# WEMOSD1R1_MATRIX64X32_RGB.net
KiCad netlist of a schematic drawn in Altium Designer
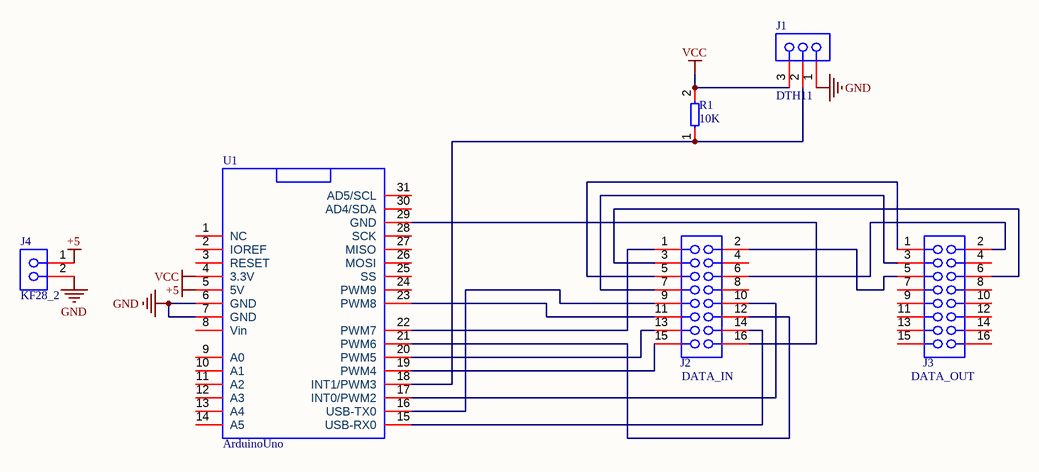
[diagram p0: WEMOSD1R1_MATRIX64X32_RGB.SchDoc]

(export (version "E")
  (design (tool "Eeschema 10.0.6"))
  (components
    (comp (ref "J1")
      (value "DTH11")
      (footprint "Header 3x1 TH Pitch 2.54mm")
      (libsource (lib "Lib31082020") (part "Header 3x1 TH Pitch 2.54mm"))
    )
    (comp (ref "J2")
      (value "DATA_IN")
      (footprint "Header 8x2 TH Pitch 2.54mm")
      (libsource (lib "Lib31082020") (part "Header 8x2 TH Pitch 2.54mm"))
    )
    (comp (ref "J3")
      (value "DATA_OUT")
      (footprint "Header 8x2 TH Pitch 2.54mm")
      (libsource (lib "Lib31082020") (part "Header 8x2 TH Pitch 2.54mm"))
    )
    (comp (ref "J4")
      (value "KF28_2")
      (footprint "HEADER_KF128_2_5.08MM")
      (libsource (lib "Lib31082020") (part "HEADER_KF128_2_5.08MM"))
    )
    (comp (ref "R1")
      (value "10K")
      (footprint "RES-0.25W-H-MF")
      (libsource (lib "Lib31082020") (part "Resistors THD"))
    )
    (comp (ref "U1")
      (value "ArduinoUno")
      (footprint "ARDUINO_UNO_PIN_PACK")
      (libsource (lib "Lib31082020") (part "ArduinoUno"))
    )
  )
  (nets
    (net (code "1") (name "+5") (class "Default")
      (node (ref "J4") (pin "1") (pinfunction "1_1") (pintype "passive"))
      (node (ref "U1") (pin "5") (pinfunction "5V_5") (pintype "passive"))
    )
    (net (code "2") (name "GND") (class "Default")
      (node (ref "J1") (pin "1") (pinfunction "1_1") (pintype "passive"))
      (node (ref "J4") (pin "2") (pinfunction "2_2") (pintype "passive"))
      (node (ref "U1") (pin "6") (pinfunction "GND_6") (pintype "passive"))
      (node (ref "U1") (pin "7") (pinfunction "GND_7") (pintype "passive"))
    )
    (net (code "3") (name "Net-(J2-Pad2)") (class "Default")
      (node (ref "J2") (pin "2") (pinfunction "2_2") (pintype "passive"))
      (node (ref "J3") (pin "5") (pinfunction "5_5") (pintype "passive"))
    )
    (net (code "4") (name "Net-(J2-Pad3)") (class "Default")
      (node (ref "J2") (pin "3") (pinfunction "3_3") (pintype "passive"))
      (node (ref "J3") (pin "6") (pinfunction "6_6") (pintype "passive"))
    )
    (net (code "5") (name "Net-(J2-Pad5)") (class "Default")
      (node (ref "J2") (pin "5") (pinfunction "5_5") (pintype "passive"))
      (node (ref "J3") (pin "1") (pinfunction "1_1") (pintype "passive"))
    )
    (net (code "6") (name "Net-(J2-Pad6)") (class "Default")
      (node (ref "J2") (pin "6") (pinfunction "6_6") (pintype "passive"))
      (node (ref "J3") (pin "2") (pinfunction "2_2") (pintype "passive"))
    )
    (net (code "7") (name "Net-(J2-Pad7)") (class "Default")
      (node (ref "J2") (pin "7") (pinfunction "7_7") (pintype "passive"))
      (node (ref "J3") (pin "3") (pinfunction "3_3") (pintype "passive"))
    )
    (net (code "8") (name "Net-(J2-Pad16)") (class "Default")
      (node (ref "J2") (pin "16") (pinfunction "16_16") (pintype "passive"))
      (node (ref "U1") (pin "29") (pinfunction "GND_29") (pintype "passive"))
    )
    (net (code "9") (name "Net-(U1-INT0{slash}PWM2)") (class "Default")
      (node (ref "J2") (pin "10") (pinfunction "10_10") (pintype "passive"))
      (node (ref "U1") (pin "17") (pinfunction "INT0/PWM2_17") (pintype "passive"))
    )
    (net (code "10") (name "Net-(U1-INT1{slash}PWM3)") (class "Default")
      (node (ref "J1") (pin "2") (pinfunction "2_2") (pintype "passive"))
      (node (ref "R1") (pin "1") (pinfunction "1_1") (pintype "passive"))
      (node (ref "U1") (pin "18") (pinfunction "INT1/PWM3_18") (pintype "passive"))
    )
    (net (code "11") (name "Net-(U1-PWM4)") (class "Default")
      (node (ref "J2") (pin "15") (pinfunction "15_15") (pintype "passive"))
      (node (ref "U1") (pin "19") (pinfunction "PWM4_19") (pintype "passive"))
    )
    (net (code "12") (name "Net-(U1-PWM5)") (class "Default")
      (node (ref "J2") (pin "13") (pinfunction "13_13") (pintype "passive"))
      (node (ref "U1") (pin "20") (pinfunction "PWM5_20") (pintype "passive"))
    )
    (net (code "13") (name "Net-(U1-PWM6)") (class "Default")
      (node (ref "J2") (pin "12") (pinfunction "12_12") (pintype "passive"))
      (node (ref "U1") (pin "21") (pinfunction "PWM6_21") (pintype "passive"))
    )
    (net (code "14") (name "Net-(U1-PWM7)") (class "Default")
      (node (ref "J2") (pin "1") (pinfunction "1_1") (pintype "passive"))
      (node (ref "U1") (pin "22") (pinfunction "PWM7_22") (pintype "passive"))
    )
    (net (code "15") (name "Net-(U1-PWM8)") (class "Default")
      (node (ref "J2") (pin "11") (pinfunction "11_11") (pintype "passive"))
      (node (ref "U1") (pin "23") (pinfunction "PWM8_23") (pintype "passive"))
    )
    (net (code "16") (name "Net-(U1-USB-RX0)") (class "Default")
      (node (ref "J2") (pin "14") (pinfunction "14_14") (pintype "passive"))
      (node (ref "U1") (pin "15") (pinfunction "USB-RX0_15") (pintype "passive"))
    )
    (net (code "17") (name "Net-(U1-USB-TX0)") (class "Default")
      (node (ref "J2") (pin "9") (pinfunction "9_9") (pintype "passive"))
      (node (ref "U1") (pin "16") (pinfunction "USB-TX0_16") (pintype "passive"))
    )
    (net (code "18") (name "VCC") (class "Default")
      (node (ref "J1") (pin "3") (pinfunction "3_3") (pintype "passive"))
      (node (ref "R1") (pin "2") (pinfunction "2_2") (pintype "passive"))
      (node (ref "U1") (pin "4") (pinfunction "3.3V_4") (pintype "passive"))
    )
    (net (code "19") (name "unconnected-(J2-Pad4)") (class "Default")
      (node (ref "J2") (pin "4") (pinfunction "4_4") (pintype "passive"))
    )
    (net (code "20") (name "unconnected-(J2-Pad8)") (class "Default")
      (node (ref "J2") (pin "8") (pinfunction "8_8") (pintype "passive"))
    )
    (net (code "21") (name "unconnected-(J3-Pad4)") (class "Default")
      (node (ref "J3") (pin "4") (pinfunction "4_4") (pintype "passive"))
    )
    (net (code "22") (name "unconnected-(J3-Pad7)") (class "Default")
      (node (ref "J3") (pin "7") (pinfunction "7_7") (pintype "passive"))
    )
    (net (code "23") (name "unconnected-(J3-Pad8)") (class "Default")
      (node (ref "J3") (pin "8") (pinfunction "8_8") (pintype "passive"))
    )
    (net (code "24") (name "unconnected-(J3-Pad9)") (class "Default")
      (node (ref "J3") (pin "9") (pinfunction "9_9") (pintype "passive"))
    )
    (net (code "25") (name "unconnected-(J3-Pad10)") (class "Default")
      (node (ref "J3") (pin "10") (pinfunction "10_10") (pintype "passive"))
    )
    (net (code "26") (name "unconnected-(J3-Pad11)") (class "Default")
      (node (ref "J3") (pin "11") (pinfunction "11_11") (pintype "passive"))
    )
    (net (code "27") (name "unconnected-(J3-Pad12)") (class "Default")
      (node (ref "J3") (pin "12") (pinfunction "12_12") (pintype "passive"))
    )
    (net (code "28") (name "unconnected-(J3-Pad13)") (class "Default")
      (node (ref "J3") (pin "13") (pinfunction "13_13") (pintype "passive"))
    )
    (net (code "29") (name "unconnected-(J3-Pad14)") (class "Default")
      (node (ref "J3") (pin "14") (pinfunction "14_14") (pintype "passive"))
    )
    (net (code "30") (name "unconnected-(J3-Pad15)") (class "Default")
      (node (ref "J3") (pin "15") (pinfunction "15_15") (pintype "passive"))
    )
    (net (code "31") (name "unconnected-(J3-Pad16)") (class "Default")
      (node (ref "J3") (pin "16") (pinfunction "16_16") (pintype "passive"))
    )
    (net (code "32") (name "unconnected-(U1-A0-Pad9)") (class "Default")
      (node (ref "U1") (pin "9") (pinfunction "A0_9") (pintype "passive"))
    )
    (net (code "33") (name "unconnected-(U1-A1-Pad10)") (class "Default")
      (node (ref "U1") (pin "10") (pinfunction "A1_10") (pintype "passive"))
    )
    (net (code "34") (name "unconnected-(U1-A2-Pad11)") (class "Default")
      (node (ref "U1") (pin "11") (pinfunction "A2_11") (pintype "passive"))
    )
    (net (code "35") (name "unconnected-(U1-A3-Pad12)") (class "Default")
      (node (ref "U1") (pin "12") (pinfunction "A3_12") (pintype "passive"))
    )
    (net (code "36") (name "unconnected-(U1-A4-Pad13)") (class "Default")
      (node (ref "U1") (pin "13") (pinfunction "A4_13") (pintype "passive"))
    )
    (net (code "37") (name "unconnected-(U1-A5-Pad14)") (class "Default")
      (node (ref "U1") (pin "14") (pinfunction "A5_14") (pintype "passive"))
    )
    (net (code "38") (name "unconnected-(U1-AD4{slash}SDA-Pad30)") (class "Default")
      (node (ref "U1") (pin "30") (pinfunction "AD4/SDA_30") (pintype "passive"))
    )
    (net (code "39") (name "unconnected-(U1-AD5{slash}SCL-Pad31)") (class "Default")
      (node (ref "U1") (pin "31") (pinfunction "AD5/SCL_31") (pintype "passive"))
    )
    (net (code "40") (name "unconnected-(U1-IOREF-Pad2)") (class "Default")
      (node (ref "U1") (pin "2") (pinfunction "IOREF_2") (pintype "passive"))
    )
    (net (code "41") (name "unconnected-(U1-MISO-Pad27)") (class "Default")
      (node (ref "U1") (pin "27") (pinfunction "MISO_27") (pintype "passive"))
    )
    (net (code "42") (name "unconnected-(U1-MOSI-Pad26)") (class "Default")
      (node (ref "U1") (pin "26") (pinfunction "MOSI_26") (pintype "passive"))
    )
    (net (code "43") (name "unconnected-(U1-NC-Pad1)") (class "Default")
      (node (ref "U1") (pin "1") (pinfunction "NC_1") (pintype "passive"))
    )
    (net (code "44") (name "unconnected-(U1-PWM9-Pad24)") (class "Default")
      (node (ref "U1") (pin "24") (pinfunction "PWM9_24") (pintype "passive"))
    )
    (net (code "45") (name "unconnected-(U1-RESET-Pad3)") (class "Default")
      (node (ref "U1") (pin "3") (pinfunction "RESET_3") (pintype "passive"))
    )
    (net (code "46") (name "unconnected-(U1-SCK-Pad28)") (class "Default")
      (node (ref "U1") (pin "28") (pinfunction "SCK_28") (pintype "passive"))
    )
    (net (code "47") (name "unconnected-(U1-SS-Pad25)") (class "Default")
      (node (ref "U1") (pin "25") (pinfunction "SS_25") (pintype "passive"))
    )
    (net (code "48") (name "unconnected-(U1-Vin-Pad8)") (class "Default")
      (node (ref "U1") (pin "8") (pinfunction "Vin_8") (pintype "passive"))
    )
  )
)
